# LO_Synthetiser.net
KiCad netlist of a schematic drawn in Altium Designer
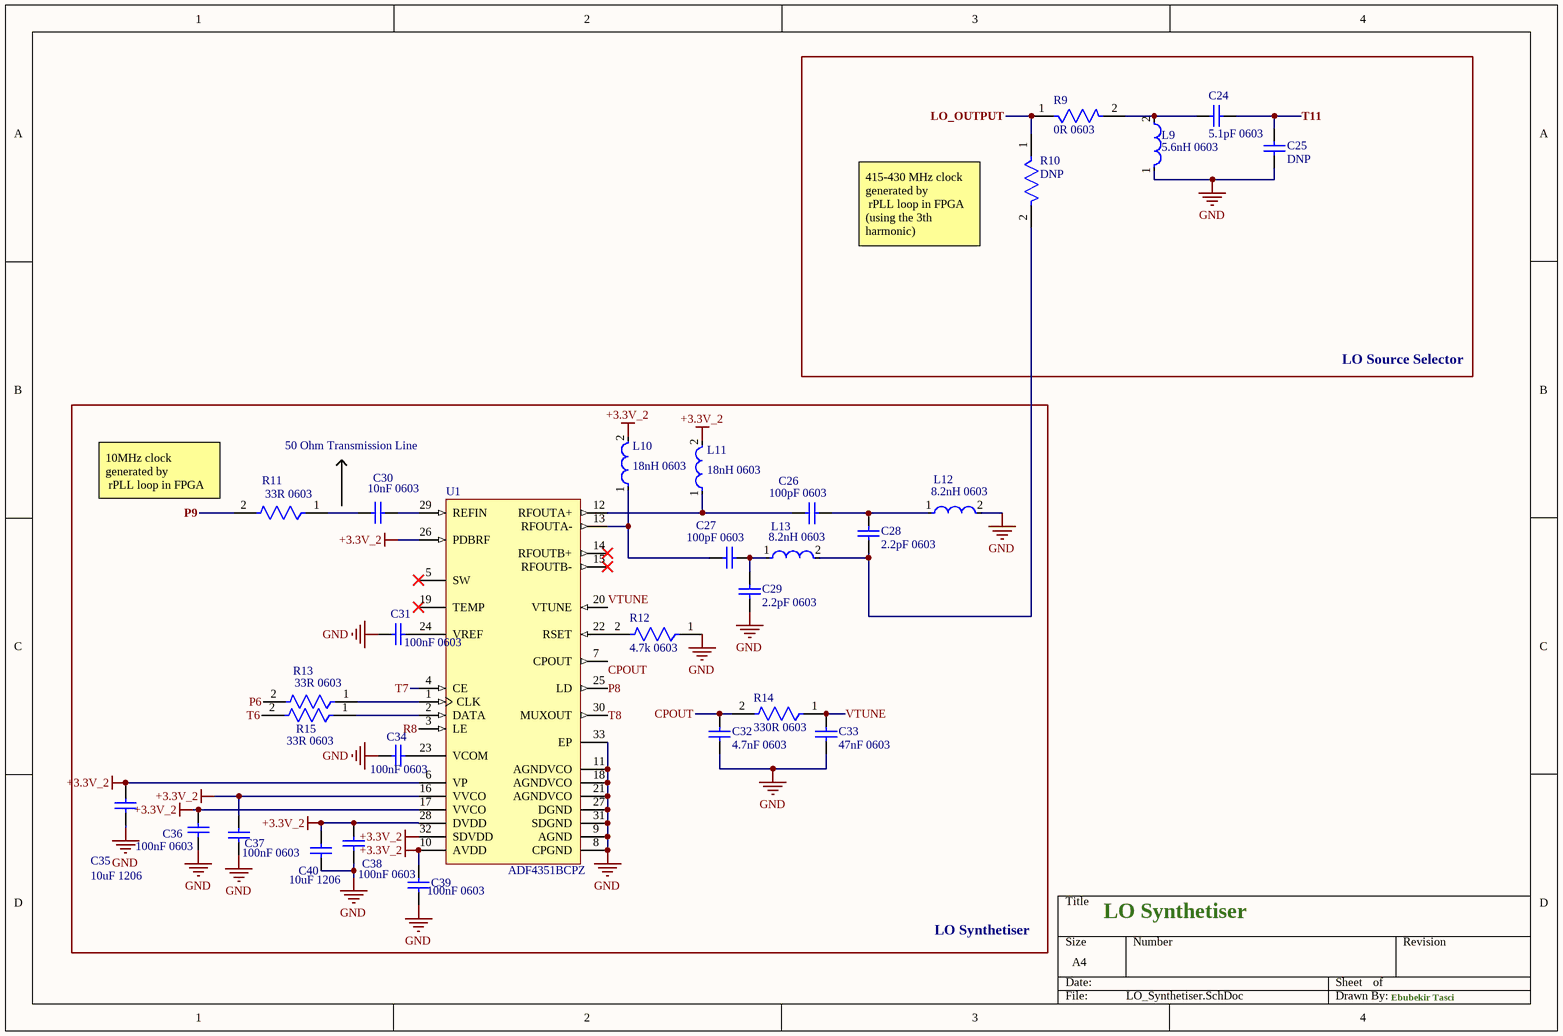
[diagram p0: LO_Synthetiser.SchDoc]

(export (version "E")
  (design (tool "Eeschema 10.0.6"))
  (components
    (comp (ref "C24")
      (value "5.1pF 0603")
      (footprint "CAPC0603(1608)100_L")
      (description "0603 5.1pF")
      (libsource (lib "Altium Content Vault") (part "CAP"))
    )
    (comp (ref "C25")
      (value "DNP")
      (footprint "CAPC0603(1608)100_L")
      (description "0603 Extra Pad")
      (libsource (lib "Altium Content Vault") (part "CAP"))
    )
    (comp (ref "C26")
      (value "100pF 0603")
      (footprint "CAPC1608X92X38LL15T08")
      (fields (field (name "MANUFACTURER") "Vitramon") (field (name "PART NUMBER") "VJ0603A101FXAAC"))
      (libsource (lib "Altium Content Vault") (part "CAP"))
    )
    (comp (ref "C27")
      (value "100pF 0603")
      (footprint "CAPC1608X92X38LL15T08")
      (fields (field (name "MANUFACTURER") "Vitramon") (field (name "PART NUMBER") "VJ0603A101FXAAC"))
      (libsource (lib "Altium Content Vault") (part "CAP"))
    )
    (comp (ref "C28")
      (value "2.2pF 0603")
      (footprint "CAPC0603(1608)100_L")
      (description "CAP 2.2pF 16V ±0.1pF 0603 (1608 Metric) Thickness 1mm SMD")
      (fields (field (name "TOLERANCE") "Â±0.1pF"))
      (libsource (lib "Altium Content Vault") (part "CAP"))
    )
    (comp (ref "C29")
      (value "2.2pF 0603")
      (footprint "CAPC0603(1608)100_L")
      (description "CAP 2.2pF 16V ±0.1pF 0603 (1608 Metric) Thickness 1mm SMD")
      (fields (field (name "TOLERANCE") "Â±0.1pF"))
      (libsource (lib "Altium Content Vault") (part "CAP"))
    )
    (comp (ref "C30")
      (value "10nF 0603")
      (footprint "CAPC0603(1608)100_L")
      (description "CAP 10nF 16V ±0.1pF 0603 (1608 Metric) Thickness 1mm SMD")
      (fields (field (name "TOLERANCE") "Â±0.1pF"))
      (libsource (lib "Altium Content Vault") (part "CAP"))
    )
    (comp (ref "C31")
      (value "100nF 0603")
      (footprint "CAPC0603(1608)100_L")
      (description "CAP 100nF 16V ±0.1pF 0603 (1608 Metric) Thickness 1mm SMD")
      (fields (field (name "TOLERANCE") "Â±0.1pF"))
      (libsource (lib "Altium Content Vault") (part "CAP"))
    )
    (comp (ref "C32")
      (value "4.7nF 0603")
      (footprint "CAPC0603(1608)100_L")
      (description "CAP 4.7nF 16V ±0.1pF 0603 (1608 Metric) Thickness 1mm SMD")
      (fields (field (name "TOLERANCE") "Â±0.1pF"))
      (libsource (lib "Altium Content Vault") (part "CAP"))
    )
    (comp (ref "C33")
      (value "47nF 0603")
      (footprint "CAPC0603(1608)100_L")
      (description "CAP 47nF 16V ±0.1pF 0603 (1608 Metric) Thickness 1mm SMD")
      (fields (field (name "TOLERANCE") "Â±0.1pF"))
      (libsource (lib "Altium Content Vault") (part "CAP"))
    )
    (comp (ref "C34")
      (value "100nF 0603")
      (footprint "CAPC0603(1608)100_L")
      (description "CAP 100nF 16V ±0.1pF 0603 (1608 Metric) Thickness 1mm SMD")
      (fields (field (name "TOLERANCE") "Â±0.1pF"))
      (libsource (lib "Altium Content Vault") (part "CAP"))
    )
    (comp (ref "C35")
      (value "10uF 1206")
      (footprint "CAPC1206(3216)190_M")
      (description "CAP 10uF 16V ±5% 1206 (3216 Metric) Thickness 1.9mm SMD")
      (fields (field (name "TOLERANCE") "Â±5%"))
      (libsource (lib "Altium Content Vault") (part "CAP"))
    )
    (comp (ref "C36")
      (value "100nF 0603")
      (footprint "CAPC0603(1608)100_L")
      (description "CAP 100nF 16V ±0.1pF 0603 (1608 Metric) Thickness 1mm SMD")
      (fields (field (name "TOLERANCE") "Â±0.1pF"))
      (libsource (lib "Altium Content Vault") (part "CAP"))
    )
    (comp (ref "C37")
      (value "100nF 0603")
      (footprint "CAPC0603(1608)100_L")
      (description "CAP 100nF 16V ±0.1pF 0603 (1608 Metric) Thickness 1mm SMD")
      (fields (field (name "TOLERANCE") "Â±0.1pF"))
      (libsource (lib "Altium Content Vault") (part "CAP"))
    )
    (comp (ref "C38")
      (value "100nF 0603")
      (footprint "CAPC0603(1608)100_L")
      (description "CAP 100nF 16V ±0.1pF 0603 (1608 Metric) Thickness 1mm SMD")
      (fields (field (name "TOLERANCE") "Â±0.1pF"))
      (libsource (lib "Altium Content Vault") (part "CAP"))
    )
    (comp (ref "C39")
      (value "100nF 0603")
      (footprint "CAPC0603(1608)100_L")
      (description "CAP 100nF 16V ±0.1pF 0603 (1608 Metric) Thickness 1mm SMD")
      (fields (field (name "TOLERANCE") "Â±0.1pF"))
      (libsource (lib "Altium Content Vault") (part "CAP"))
    )
    (comp (ref "C40")
      (value "10uF 1206")
      (footprint "CAPC1206(3216)190_M")
      (description "CAP 10uF 16V ±5% 1206 (3216 Metric) Thickness 1.9mm SMD")
      (fields (field (name "TOLERANCE") "Â±5%"))
      (libsource (lib "Altium Content Vault") (part "CAP"))
    )
    (comp (ref "L9")
      (value "5.6nH 0603")
      (footprint "FP-AISC-0603HP-MFG")
      (description "5.6nH Wirewound 0603")
      (libsource (lib "") (part "725321dda6339637d4d059423bc1c3c_1"))
    )
    (comp (ref "L10")
      (value "18nH 0603")
      (footprint "FP-AISC-0603HP-MFG")
      (description "18nH Wirewound 0603")
      (libsource (lib "Altium Content Vault") (part "725321dda6339637d4d059423bc1c3c"))
    )
    (comp (ref "L11")
      (value "18nH 0603")
      (footprint "FP-AISC-0603HP-MFG")
      (description "18nH Wirewound 0603")
      (libsource (lib "Altium Content Vault") (part "725321dda6339637d4d059423bc1c3c"))
    )
    (comp (ref "L12")
      (value "8.2nH 0603")
      (footprint "FP-AISC-0603HP-MFG")
      (description "FIXED IND 8.2NH SMD")
      (fields (field (name "TOLERANCE") "5%"))
      (libsource (lib "Altium Content Vault") (part "725321dda6339637d4d059423bc1c3c"))
    )
    (comp (ref "L13")
      (value "8.2nH 0603")
      (footprint "FP-AISC-0603HP-MFG")
      (description "FIXED IND 8.2NH SMD")
      (fields (field (name "TOLERANCE") "5%"))
      (libsource (lib "Altium Content Vault") (part "725321dda6339637d4d059423bc1c3c"))
    )
    (comp (ref "R9")
      (value "0R 0603")
      (footprint "FP-CPF0603-MFG")
      (description "RES SMD 0Ω 0.1% 1/16W 0603")
      (fields
        (field (name "OCTOPART") "https://octopart.com/cpf0603b430re1-te+connectivity-22738753")
        (field (name "MANUFACTURER PART NUMBER") "CPF0603B430RE1")
      )
      (libsource (lib "Altium Content Vault") (part "1029c3af85768c4190bb7ad29bc67b5"))
    )
    (comp (ref "R10")
      (value "DNP")
      (footprint "FP-CPF0603-MFG")
      (fields
        (field (name "OCTOPART") "https://octopart.com/cpf0603b430re1-te+connectivity-22738753")
        (field (name "MANUFACTURER PART NUMBER") "CPF0603B430RE1")
        (field (name "TOLERANCE") "0.1%")
      )
      (libsource (lib "Altium Content Vault") (part "1029c3af85768c4190bb7ad29bc67b5"))
    )
    (comp (ref "R11")
      (value "33R 0603")
      (footprint "FP-CPF0603-MFG")
      (description "RES SMD 33Ω 0.1% 1/16W 0603")
      (fields
        (field (name "OCTOPART") "https://octopart.com/cpf0603b430re1-te+connectivity-22738753")
        (field (name "MANUFACTURER PART NUMBER") "CPF0603B430RE1")
      )
      (libsource (lib "Altium Content Vault") (part "1029c3af85768c4190bb7ad29bc67b5"))
    )
    (comp (ref "R12")
      (value "4.7k 0603")
      (footprint "FP-CPF0603-MFG")
      (description "RES SMD 4.7kΩ 0.1% 1/16W 0603")
      (fields (field (name "TOLERANCE") "0.1%") (field (name "MANUFACTURER") "TE Connectivity"))
      (libsource (lib "Altium Content Vault") (part "1029c3af85768c4190bb7ad29bc67b5"))
    )
    (comp (ref "R13")
      (value "33R 0603")
      (footprint "FP-CPF0603-MFG")
      (description "RES SMD 33Ω 0.1% 1/16W 0603")
      (fields
        (field (name "OCTOPART") "https://octopart.com/cpf0603b430re1-te+connectivity-22738753")
        (field (name "MANUFACTURER PART NUMBER") "CPF0603B430RE1")
      )
      (libsource (lib "Altium Content Vault") (part "1029c3af85768c4190bb7ad29bc67b5"))
    )
    (comp (ref "R14")
      (value "330R 0603")
      (footprint "FP-CPF0603-MFG")
      (description "RES SMD 330Ω 0.1% 1/16W 0603")
      (fields (field (name "TOLERANCE") "0.1%") (field (name "MANUFACTURER") "TE Connectivity"))
      (libsource (lib "Altium Content Vault") (part "1029c3af85768c4190bb7ad29bc67b5"))
    )
    (comp (ref "R15")
      (value "33R 0603")
      (footprint "FP-CPF0603-MFG")
      (description "RES SMD 33Ω 0.1% 1/16W 0603")
      (fields
        (field (name "OCTOPART") "https://octopart.com/cpf0603b430re1-te+connectivity-22738753")
        (field (name "MANUFACTURER PART NUMBER") "CPF0603B430RE1")
      )
      (libsource (lib "Altium Content Vault") (part "1029c3af85768c4190bb7ad29bc67b5"))
    )
    (comp (ref "U1")
      (value "ADF4351BCPZ")
      (footprint "ADI-CP-32-2_N")
      (description "Wideband Synthesizer with Integrated VCO, CP-32-2, Pb-Free, 490 Tray")
      (libsource (lib "Altium Content Vault") (part "ADI-ADF4351-CP-32-2"))
    )
  )
  (nets
    (net (code "1") (name "+3.3V_2") (class "Default")
      (node (ref "C35") (pin "1") (pinfunction "1_1") (pintype "passive"))
      (node (ref "C36") (pin "1") (pinfunction "1_1") (pintype "passive"))
      (node (ref "C37") (pin "1") (pinfunction "1_1") (pintype "passive"))
      (node (ref "C38") (pin "1") (pinfunction "1_1") (pintype "passive"))
      (node (ref "C39") (pin "1") (pinfunction "1_1") (pintype "passive"))
      (node (ref "C40") (pin "2") (pinfunction "2_2") (pintype "passive"))
      (node (ref "L10") (pin "2") (pinfunction "2_2") (pintype "passive"))
      (node (ref "L11") (pin "2") (pinfunction "2_2") (pintype "passive"))
      (node (ref "U1") (pin "10") (pinfunction "AVDD_10") (pintype "power_in"))
      (node (ref "U1") (pin "16") (pinfunction "VVCO_16") (pintype "power_in"))
      (node (ref "U1") (pin "17") (pinfunction "VVCO_17") (pintype "power_in"))
      (node (ref "U1") (pin "26") (pinfunction "PDBRF_26") (pintype "input"))
      (node (ref "U1") (pin "28") (pinfunction "DVDD_28") (pintype "power_in"))
      (node (ref "U1") (pin "32") (pinfunction "SDVDD_32") (pintype "power_in"))
      (node (ref "U1") (pin "6") (pinfunction "VP_6") (pintype "power_in"))
    )
    (net (code "2") (name "/CPOUT") (class "Default")
      (node (ref "C32") (pin "1") (pinfunction "1_1") (pintype "passive"))
      (node (ref "R14") (pin "2") (pinfunction "2_2") (pintype "passive"))
      (node (ref "U1") (pin "7") (pinfunction "CPOUT_7") (pintype "output"))
    )
    (net (code "3") (name "/LO_OUTPUT") (class "Default")
      (node (ref "R10") (pin "1") (pinfunction "1_1") (pintype "passive"))
      (node (ref "R9") (pin "1") (pinfunction "1_1") (pintype "passive"))
    )
    (net (code "4") (name "/P6") (class "Default")
      (node (ref "R13") (pin "2") (pinfunction "2_2") (pintype "passive"))
    )
    (net (code "5") (name "/P8") (class "Default")
      (node (ref "U1") (pin "25") (pinfunction "LD_25") (pintype "output"))
    )
    (net (code "6") (name "/P9") (class "Default")
      (node (ref "R11") (pin "2") (pinfunction "2_2") (pintype "passive"))
    )
    (net (code "7") (name "/R8") (class "Default")
      (node (ref "U1") (pin "3") (pinfunction "LE_3") (pintype "input"))
    )
    (net (code "8") (name "/T6") (class "Default")
      (node (ref "R15") (pin "2") (pinfunction "2_2") (pintype "passive"))
    )
    (net (code "9") (name "/T7") (class "Default")
      (node (ref "U1") (pin "4") (pinfunction "CE_4") (pintype "input"))
    )
    (net (code "10") (name "/T8") (class "Default")
      (node (ref "U1") (pin "30") (pinfunction "MUXOUT_30") (pintype "output"))
    )
    (net (code "11") (name "/T11") (class "Default")
      (node (ref "C24") (pin "2") (pinfunction "2_2") (pintype "passive"))
      (node (ref "C25") (pin "2") (pinfunction "2_2") (pintype "passive"))
    )
    (net (code "12") (name "/VTUNE") (class "Default")
      (node (ref "C33") (pin "1") (pinfunction "1_1") (pintype "passive"))
      (node (ref "R14") (pin "1") (pinfunction "1_1") (pintype "passive"))
      (node (ref "U1") (pin "20") (pinfunction "VTUNE_20") (pintype "input"))
    )
    (net (code "13") (name "GND") (class "Default")
      (node (ref "C25") (pin "1") (pinfunction "1_1") (pintype "passive"))
      (node (ref "C29") (pin "1") (pinfunction "1_1") (pintype "passive"))
      (node (ref "C31") (pin "2") (pinfunction "2_2") (pintype "passive"))
      (node (ref "C32") (pin "2") (pinfunction "2_2") (pintype "passive"))
      (node (ref "C33") (pin "2") (pinfunction "2_2") (pintype "passive"))
      (node (ref "C34") (pin "2") (pinfunction "2_2") (pintype "passive"))
      (node (ref "C35") (pin "2") (pinfunction "2_2") (pintype "passive"))
      (node (ref "C36") (pin "2") (pinfunction "2_2") (pintype "passive"))
      (node (ref "C37") (pin "2") (pinfunction "2_2") (pintype "passive"))
      (node (ref "C38") (pin "2") (pinfunction "2_2") (pintype "passive"))
      (node (ref "C39") (pin "2") (pinfunction "2_2") (pintype "passive"))
      (node (ref "C40") (pin "1") (pinfunction "1_1") (pintype "passive"))
      (node (ref "L12") (pin "2") (pinfunction "2_2") (pintype "passive"))
      (node (ref "L9") (pin "1") (pinfunction "1_1") (pintype "passive"))
      (node (ref "R12") (pin "1") (pinfunction "1_1") (pintype "passive"))
      (node (ref "U1") (pin "11") (pinfunction "AGNDVCO_11") (pintype "power_in"))
      (node (ref "U1") (pin "18") (pinfunction "AGNDVCO_18") (pintype "power_in"))
      (node (ref "U1") (pin "21") (pinfunction "AGNDVCO_21") (pintype "power_in"))
      (node (ref "U1") (pin "27") (pinfunction "DGND_27") (pintype "power_in"))
      (node (ref "U1") (pin "31") (pinfunction "SDGND_31") (pintype "power_in"))
      (node (ref "U1") (pin "33") (pinfunction "EP_33") (pintype "power_in"))
      (node (ref "U1") (pin "8") (pinfunction "CPGND_8") (pintype "power_in"))
      (node (ref "U1") (pin "9") (pinfunction "AGND_9") (pintype "power_in"))
    )
    (net (code "14") (name "Net-(C24-Pad1)") (class "Default")
      (node (ref "C24") (pin "1") (pinfunction "1_1") (pintype "passive"))
      (node (ref "L9") (pin "2") (pinfunction "2_2") (pintype "passive"))
      (node (ref "R9") (pin "2") (pinfunction "2_2") (pintype "passive"))
    )
    (net (code "15") (name "Net-(C26-Pad2)") (class "Default")
      (node (ref "C26") (pin "2") (pinfunction "2_2") (pintype "passive"))
      (node (ref "C28") (pin "2") (pinfunction "2_2") (pintype "passive"))
      (node (ref "L12") (pin "1") (pinfunction "1_1") (pintype "passive"))
    )
    (net (code "16") (name "Net-(C27-Pad2)") (class "Default")
      (node (ref "C27") (pin "2") (pinfunction "2_2") (pintype "passive"))
      (node (ref "C29") (pin "2") (pinfunction "2_2") (pintype "passive"))
      (node (ref "L13") (pin "1") (pinfunction "1_1") (pintype "passive"))
    )
    (net (code "17") (name "Net-(C28-Pad1)") (class "Default")
      (node (ref "C28") (pin "1") (pinfunction "1_1") (pintype "passive"))
      (node (ref "L13") (pin "2") (pinfunction "2_2") (pintype "passive"))
      (node (ref "R10") (pin "2") (pinfunction "2_2") (pintype "passive"))
    )
    (net (code "18") (name "Net-(C30-Pad2)") (class "Default")
      (node (ref "C30") (pin "2") (pinfunction "2_2") (pintype "passive"))
      (node (ref "R11") (pin "1") (pinfunction "1_1") (pintype "passive"))
    )
    (net (code "19") (name "Net-(U1-CLK)") (class "Default")
      (node (ref "R13") (pin "1") (pinfunction "1_1") (pintype "passive"))
      (node (ref "U1") (pin "1") (pinfunction "CLK_1") (pintype "input"))
    )
    (net (code "20") (name "Net-(U1-DATA)") (class "Default")
      (node (ref "R15") (pin "1") (pinfunction "1_1") (pintype "passive"))
      (node (ref "U1") (pin "2") (pinfunction "DATA_2") (pintype "input"))
    )
    (net (code "21") (name "Net-(U1-REFIN)") (class "Default")
      (node (ref "C30") (pin "1") (pinfunction "1_1") (pintype "passive"))
      (node (ref "U1") (pin "29") (pinfunction "REFIN_29") (pintype "input"))
    )
    (net (code "22") (name "Net-(U1-RFOUTA+)") (class "Default")
      (node (ref "C26") (pin "1") (pinfunction "1_1") (pintype "passive"))
      (node (ref "L11") (pin "1") (pinfunction "1_1") (pintype "passive"))
      (node (ref "U1") (pin "12") (pinfunction "RFOUTA+_12") (pintype "output"))
    )
    (net (code "23") (name "Net-(U1-RFOUTA-)") (class "Default")
      (node (ref "C27") (pin "1") (pinfunction "1_1") (pintype "passive"))
      (node (ref "L10") (pin "1") (pinfunction "1_1") (pintype "passive"))
      (node (ref "U1") (pin "13") (pinfunction "RFOUTA-_13") (pintype "output"))
    )
    (net (code "24") (name "Net-(U1-RSET)") (class "Default")
      (node (ref "R12") (pin "2") (pinfunction "2_2") (pintype "passive"))
      (node (ref "U1") (pin "22") (pinfunction "RSET_22") (pintype "input"))
    )
    (net (code "25") (name "Net-(U1-VCOM)") (class "Default")
      (node (ref "C34") (pin "1") (pinfunction "1_1") (pintype "passive"))
      (node (ref "U1") (pin "23") (pinfunction "VCOM_23") (pintype "passive"))
    )
    (net (code "26") (name "Net-(U1-VREF)") (class "Default")
      (node (ref "C31") (pin "1") (pinfunction "1_1") (pintype "passive"))
      (node (ref "U1") (pin "24") (pinfunction "VREF_24") (pintype "passive"))
    )
    (net (code "27") (name "unconnected-(U1-RFOUTB+-Pad14)") (class "Default")
      (node (ref "U1") (pin "14") (pinfunction "RFOUTB+_14") (pintype "output+no_connect"))
    )
    (net (code "28") (name "unconnected-(U1-RFOUTB--Pad15)") (class "Default")
      (node (ref "U1") (pin "15") (pinfunction "RFOUTB-_15") (pintype "output+no_connect"))
    )
    (net (code "29") (name "unconnected-(U1-SW-Pad5)") (class "Default")
      (node (ref "U1") (pin "5") (pinfunction "SW_5") (pintype "passive+no_connect"))
    )
    (net (code "30") (name "unconnected-(U1-TEMP-Pad19)") (class "Default")
      (node (ref "U1") (pin "19") (pinfunction "TEMP_19") (pintype "passive+no_connect"))
    )
  )
)
